# SCH_CHIPI_RELAY.net
KiCad netlist of a schematic drawn in Altium Designer
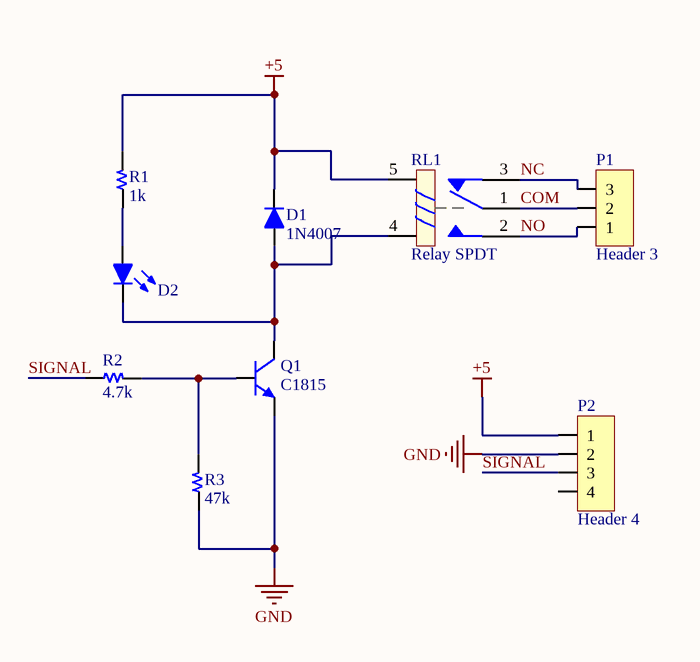
[diagram p0: SCH_CHIPI_RELAY.SchDoc]

(export (version "E")
  (design (tool "Eeschema 10.0.6"))
  (components
    (comp (ref "D1")
      (value "1N4007")
      (footprint "Diode PowerDI123")
      (description "Default Diode")
      (libsource (lib "chipfc_libs") (part "Diode"))
    )
    (comp (ref "D2")
      (value "Led")
      (footprint "Led 0805 RED")
      (description "Typical LED")
      (libsource (lib "chipfc_libs") (part "Led"))
    )
    (comp (ref "P1")
      (value "Header 3")
      (footprint "HDR/Terminal/3")
      (description "Header, 3-Pin")
      (libsource (lib "connectors") (part "Header 3"))
    )
    (comp (ref "P2")
      (value "Header 4")
      (footprint "HDR/Header/4/BOX/RED")
      (description "Header, 4-Pin")
      (libsource (lib "connectors") (part "Header 4"))
    )
    (comp (ref "Q1")
      (value "C1815")
      (footprint "SOT-23")
      (description "NPN Bipolar Transistor")
      (libsource (lib "chipfc_libs") (part "Transistor NPN"))
    )
    (comp (ref "R1")
      (value "1k")
      (footprint "R 0805")
      (description "Resistor")
      (libsource (lib "chipfc_libs") (part "Resistor"))
    )
    (comp (ref "R2")
      (value "4.7k")
      (footprint "R 0805")
      (description "Resistor")
      (libsource (lib "chipfc_libs") (part "Resistor"))
    )
    (comp (ref "R3")
      (value "47k")
      (footprint "R 0805")
      (description "Resistor")
      (libsource (lib "chipfc_libs") (part "Resistor"))
    )
    (comp (ref "RL1")
      (value "Relay SPDT")
      (footprint "RL_SPDT_10A")
      (libsource (lib "chipfc_libs") (part "Relay SPDT"))
    )
  )
  (nets
    (net (code "1") (name "+5") (class "Default")
      (node (ref "D1") (pin "2") (pinfunction "K_2") (pintype "passive"))
      (node (ref "P2") (pin "1") (pinfunction "1_1") (pintype "passive"))
      (node (ref "R1") (pin "2") (pinfunction "2_2") (pintype "passive"))
      (node (ref "RL1") (pin "5") (pinfunction "COIL2_5") (pintype "passive"))
    )
    (net (code "2") (name "/COM") (class "Default")
      (node (ref "P1") (pin "2") (pinfunction "2_2") (pintype "passive"))
      (node (ref "RL1") (pin "1") (pinfunction "COM_1") (pintype "passive"))
    )
    (net (code "3") (name "/NC") (class "Default")
      (node (ref "P1") (pin "3") (pinfunction "3_3") (pintype "passive"))
      (node (ref "RL1") (pin "3") (pinfunction "NC_3") (pintype "passive"))
    )
    (net (code "4") (name "/NO") (class "Default")
      (node (ref "P1") (pin "1") (pinfunction "1_1") (pintype "passive"))
      (node (ref "RL1") (pin "2") (pinfunction "NO_2") (pintype "passive"))
    )
    (net (code "5") (name "/SIGNAL") (class "Default")
      (node (ref "P2") (pin "3") (pinfunction "3_3") (pintype "passive"))
      (node (ref "R2") (pin "1") (pinfunction "1_1") (pintype "passive"))
    )
    (net (code "6") (name "GND") (class "Default")
      (node (ref "P2") (pin "2") (pinfunction "2_2") (pintype "passive"))
      (node (ref "Q1") (pin "2") (pinfunction "E_2") (pintype "passive"))
      (node (ref "R3") (pin "1") (pinfunction "1_1") (pintype "passive"))
    )
    (net (code "7") (name "Net-(D1-A)") (class "Default")
      (node (ref "D1") (pin "1") (pinfunction "A_1") (pintype "passive"))
      (node (ref "D2") (pin "2") (pinfunction "K_2") (pintype "passive"))
      (node (ref "Q1") (pin "3") (pinfunction "C_3") (pintype "passive"))
      (node (ref "RL1") (pin "4") (pinfunction "COIL1_4") (pintype "passive"))
    )
    (net (code "8") (name "Net-(D2-A)") (class "Default")
      (node (ref "D2") (pin "1") (pinfunction "A_1") (pintype "passive"))
      (node (ref "R1") (pin "1") (pinfunction "1_1") (pintype "passive"))
    )
    (net (code "9") (name "Net-(Q1-B)") (class "Default")
      (node (ref "Q1") (pin "1") (pinfunction "B_1") (pintype "passive"))
      (node (ref "R2") (pin "2") (pinfunction "2_2") (pintype "passive"))
      (node (ref "R3") (pin "2") (pinfunction "2_2") (pintype "passive"))
    )
    (net (code "10") (name "unconnected-(P2-Pad4)") (class "Default")
      (node (ref "P2") (pin "4") (pinfunction "4_4") (pintype "passive"))
    )
  )
)
